# CAN_Star.net
KiCad netlist of a schematic drawn in EAGLE
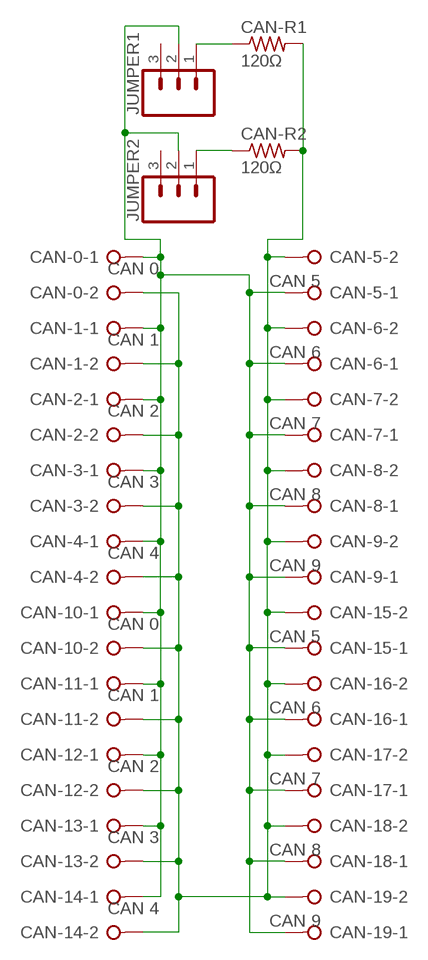
[diagram p0: schematic, sheet 1]

(export (version "E")
  (design (tool "Eeschema 10.0.6"))
  (components
    (comp (ref "CAN-0")
      (value "CAN 0")
      (footprint "eagle-import:W237-132")
      (libsource (lib "eagle-import") (part "W237-02P"))
    )
    (comp (ref "CAN-1")
      (value "CAN 1")
      (footprint "eagle-import:W237-132")
      (libsource (lib "eagle-import") (part "W237-02P"))
    )
    (comp (ref "CAN-2")
      (value "CAN 2")
      (footprint "eagle-import:W237-132")
      (libsource (lib "eagle-import") (part "W237-02P"))
    )
    (comp (ref "CAN-3")
      (value "CAN 3")
      (footprint "eagle-import:W237-132")
      (libsource (lib "eagle-import") (part "W237-02P"))
    )
    (comp (ref "CAN-4")
      (value "CAN 4")
      (footprint "eagle-import:W237-132")
      (libsource (lib "eagle-import") (part "W237-02P"))
    )
    (comp (ref "CAN-5")
      (value "CAN 5")
      (footprint "eagle-import:W237-132")
      (libsource (lib "eagle-import") (part "W237-02P"))
    )
    (comp (ref "CAN-6")
      (value "CAN 6")
      (footprint "eagle-import:W237-132")
      (libsource (lib "eagle-import") (part "W237-02P"))
    )
    (comp (ref "CAN-7")
      (value "CAN 7")
      (footprint "eagle-import:W237-132")
      (libsource (lib "eagle-import") (part "W237-02P"))
    )
    (comp (ref "CAN-8")
      (value "CAN 8")
      (footprint "eagle-import:W237-132")
      (libsource (lib "eagle-import") (part "W237-02P"))
    )
    (comp (ref "CAN-9")
      (value "CAN 9")
      (footprint "eagle-import:W237-132")
      (libsource (lib "eagle-import") (part "W237-02P"))
    )
    (comp (ref "CAN-10")
      (value "CAN 0")
      (footprint "eagle-import:W237-132")
      (libsource (lib "eagle-import") (part "W237-02P"))
    )
    (comp (ref "CAN-11")
      (value "CAN 1")
      (footprint "eagle-import:W237-132")
      (libsource (lib "eagle-import") (part "W237-02P"))
    )
    (comp (ref "CAN-12")
      (value "CAN 2")
      (footprint "eagle-import:W237-132")
      (libsource (lib "eagle-import") (part "W237-02P"))
    )
    (comp (ref "CAN-13")
      (value "CAN 3")
      (footprint "eagle-import:W237-132")
      (libsource (lib "eagle-import") (part "W237-02P"))
    )
    (comp (ref "CAN-14")
      (value "CAN 4")
      (footprint "eagle-import:W237-132")
      (libsource (lib "eagle-import") (part "W237-02P"))
    )
    (comp (ref "CAN-15")
      (value "CAN 5")
      (footprint "eagle-import:W237-132")
      (libsource (lib "eagle-import") (part "W237-02P"))
    )
    (comp (ref "CAN-16")
      (value "CAN 6")
      (footprint "eagle-import:W237-132")
      (libsource (lib "eagle-import") (part "W237-02P"))
    )
    (comp (ref "CAN-17")
      (value "CAN 7")
      (footprint "eagle-import:W237-132")
      (libsource (lib "eagle-import") (part "W237-02P"))
    )
    (comp (ref "CAN-18")
      (value "CAN 8")
      (footprint "eagle-import:W237-132")
      (libsource (lib "eagle-import") (part "W237-02P"))
    )
    (comp (ref "CAN-19")
      (value "CAN 9")
      (footprint "eagle-import:W237-132")
      (libsource (lib "eagle-import") (part "W237-02P"))
    )
    (comp (ref "CAN-R1")
      (value "120Ω")
      (footprint "eagle-import:0207_10")
      (libsource (lib "eagle-import") (part "R-US_0207/10"))
    )
    (comp (ref "CAN-R2")
      (value "120Ω")
      (footprint "eagle-import:0207_10")
      (libsource (lib "eagle-import") (part "R-US_0207/10"))
    )
    (comp (ref "JUMPER1")
      (value "CONN_03")
      (footprint "eagle-import:1X03")
      (libsource (lib "eagle-import") (part "CONN_03"))
    )
    (comp (ref "JUMPER2")
      (value "CONN_03")
      (footprint "eagle-import:1X03")
      (libsource (lib "eagle-import") (part "CONN_03"))
    )
  )
  (nets
    (net (code "1") (name "Net-(CAN-0A-KL)") (class "Default")
      (node (ref "CAN-0") (pin "1") (pinfunction "KL_1") (pintype "passive"))
      (node (ref "CAN-1") (pin "1") (pinfunction "KL_1") (pintype "passive"))
      (node (ref "CAN-10") (pin "1") (pinfunction "KL_1") (pintype "passive"))
      (node (ref "CAN-11") (pin "1") (pinfunction "KL_1") (pintype "passive"))
      (node (ref "CAN-12") (pin "1") (pinfunction "KL_1") (pintype "passive"))
      (node (ref "CAN-13") (pin "1") (pinfunction "KL_1") (pintype "passive"))
      (node (ref "CAN-14") (pin "1") (pinfunction "KL_1") (pintype "passive"))
      (node (ref "CAN-15") (pin "1") (pinfunction "KL_1") (pintype "passive"))
      (node (ref "CAN-16") (pin "1") (pinfunction "KL_1") (pintype "passive"))
      (node (ref "CAN-17") (pin "1") (pinfunction "KL_1") (pintype "passive"))
      (node (ref "CAN-18") (pin "1") (pinfunction "KL_1") (pintype "passive"))
      (node (ref "CAN-19") (pin "1") (pinfunction "KL_1") (pintype "passive"))
      (node (ref "CAN-2") (pin "1") (pinfunction "KL_1") (pintype "passive"))
      (node (ref "CAN-3") (pin "1") (pinfunction "KL_1") (pintype "passive"))
      (node (ref "CAN-4") (pin "1") (pinfunction "KL_1") (pintype "passive"))
      (node (ref "CAN-5") (pin "1") (pinfunction "KL_1") (pintype "passive"))
      (node (ref "CAN-6") (pin "1") (pinfunction "KL_1") (pintype "passive"))
      (node (ref "CAN-7") (pin "1") (pinfunction "KL_1") (pintype "passive"))
      (node (ref "CAN-8") (pin "1") (pinfunction "KL_1") (pintype "passive"))
      (node (ref "CAN-9") (pin "1") (pinfunction "KL_1") (pintype "passive"))
      (node (ref "JUMPER1") (pin "2") (pinfunction "2_2") (pintype "passive"))
      (node (ref "JUMPER2") (pin "2") (pinfunction "2_2") (pintype "passive"))
    )
    (net (code "2") (name "Net-(CAN-0B-KL)") (class "Default")
      (node (ref "CAN-0") (pin "2") (pinfunction "KL_2") (pintype "passive"))
      (node (ref "CAN-1") (pin "2") (pinfunction "KL_2") (pintype "passive"))
      (node (ref "CAN-10") (pin "2") (pinfunction "KL_2") (pintype "passive"))
      (node (ref "CAN-11") (pin "2") (pinfunction "KL_2") (pintype "passive"))
      (node (ref "CAN-12") (pin "2") (pinfunction "KL_2") (pintype "passive"))
      (node (ref "CAN-13") (pin "2") (pinfunction "KL_2") (pintype "passive"))
      (node (ref "CAN-14") (pin "2") (pinfunction "KL_2") (pintype "passive"))
      (node (ref "CAN-15") (pin "2") (pinfunction "KL_2") (pintype "passive"))
      (node (ref "CAN-16") (pin "2") (pinfunction "KL_2") (pintype "passive"))
      (node (ref "CAN-17") (pin "2") (pinfunction "KL_2") (pintype "passive"))
      (node (ref "CAN-18") (pin "2") (pinfunction "KL_2") (pintype "passive"))
      (node (ref "CAN-19") (pin "2") (pinfunction "KL_2") (pintype "passive"))
      (node (ref "CAN-2") (pin "2") (pinfunction "KL_2") (pintype "passive"))
      (node (ref "CAN-3") (pin "2") (pinfunction "KL_2") (pintype "passive"))
      (node (ref "CAN-4") (pin "2") (pinfunction "KL_2") (pintype "passive"))
      (node (ref "CAN-5") (pin "2") (pinfunction "KL_2") (pintype "passive"))
      (node (ref "CAN-6") (pin "2") (pinfunction "KL_2") (pintype "passive"))
      (node (ref "CAN-7") (pin "2") (pinfunction "KL_2") (pintype "passive"))
      (node (ref "CAN-8") (pin "2") (pinfunction "KL_2") (pintype "passive"))
      (node (ref "CAN-9") (pin "2") (pinfunction "KL_2") (pintype "passive"))
      (node (ref "CAN-R1") (pin "2") (pinfunction "2_2") (pintype "passive"))
      (node (ref "CAN-R2") (pin "2") (pinfunction "2_2") (pintype "passive"))
    )
    (net (code "3") (name "Net-(CAN-R1-Pad1)") (class "Default")
      (node (ref "CAN-R1") (pin "1") (pinfunction "1_1") (pintype "passive"))
      (node (ref "JUMPER1") (pin "1") (pinfunction "1_1") (pintype "passive"))
    )
    (net (code "4") (name "Net-(CAN-R2-Pad1)") (class "Default")
      (node (ref "CAN-R2") (pin "1") (pinfunction "1_1") (pintype "passive"))
      (node (ref "JUMPER2") (pin "1") (pinfunction "1_1") (pintype "passive"))
    )
    (net (code "5") (name "unconnected-(JUMPER1-Pad3)") (class "Default")
      (node (ref "JUMPER1") (pin "3") (pinfunction "3_3") (pintype "passive"))
    )
    (net (code "6") (name "unconnected-(JUMPER2-Pad3)") (class "Default")
      (node (ref "JUMPER2") (pin "3") (pinfunction "3_3") (pintype "passive"))
    )
  )
)
